# PCIe-M2.net
KiCad netlist of a schematic drawn in Altium Designer
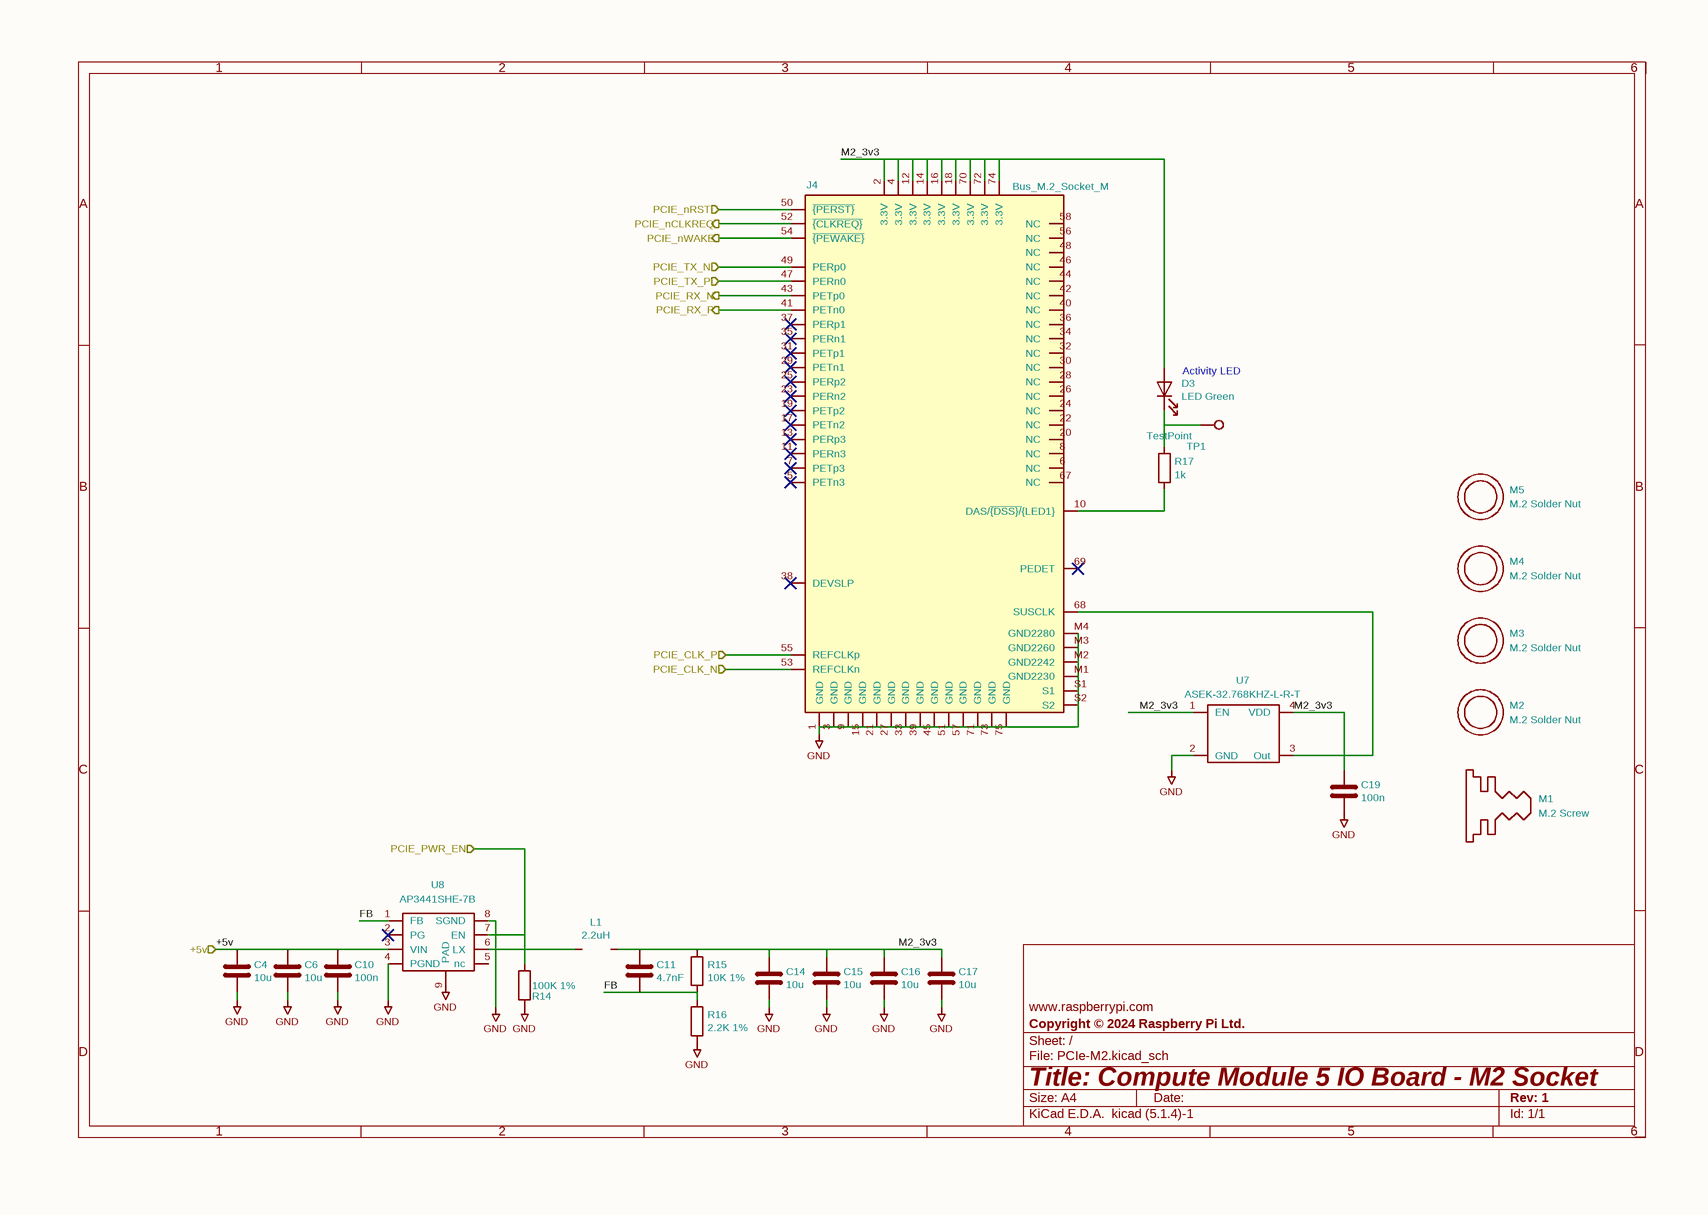
[diagram p0: PCIe-M2.SchDoc]

(export (version "E")
  (design (tool "Eeschema 10.0.6"))
  (components
    (comp (ref "C4") (value "10u") (libsource (lib "Device") (part "C")))
    (comp (ref "C6") (value "10u") (libsource (lib "Device") (part "C")))
    (comp (ref "C10") (value "100n") (libsource (lib "Device") (part "C")))
    (comp (ref "C11") (value "4.7nF") (libsource (lib "Device") (part "C")))
    (comp (ref "C14") (value "10u") (libsource (lib "Device") (part "C")))
    (comp (ref "C15") (value "10u") (libsource (lib "Device") (part "C")))
    (comp (ref "C16") (value "10u") (libsource (lib "Device") (part "C")))
    (comp (ref "C17") (value "10u") (libsource (lib "Device") (part "C")))
    (comp (ref "C19") (value "100n") (libsource (lib "Device") (part "C")))
    (comp (ref "D3") (value "LED Green") (libsource (lib "Device") (part "LED")))
    (comp (ref "J4")
      (value "Bus_M.2_Socket_M")
      (description "M.2 Socket 3 Mechanical Key M")
      (libsource (lib "CM5IO") (part "Bus_M.2_Socket_M"))
    )
    (comp (ref "L1") (value "2.2uH") (libsource (lib "Device") (part "L")))
    (comp (ref "M1") (value "M.2 Screw") (libsource (lib "CM5IO") (part "M.2_Screw")))
    (comp (ref "M2") (value "M.2 Solder Nut") (libsource (lib "CM5IO") (part "SolderNut")))
    (comp (ref "M3") (value "M.2 Solder Nut") (libsource (lib "CM5IO") (part "SolderNut")))
    (comp (ref "M4") (value "M.2 Solder Nut") (libsource (lib "CM5IO") (part "SolderNut")))
    (comp (ref "M5") (value "M.2 Solder Nut") (libsource (lib "CM5IO") (part "SolderNut")))
    (comp (ref "R14") (value "100K 1%") (libsource (lib "Device") (part "R")))
    (comp (ref "R15") (value "10K 1%") (libsource (lib "Device") (part "R")))
    (comp (ref "R16") (value "2.2K 1%") (libsource (lib "Device") (part "R")))
    (comp (ref "R17") (value "1k") (libsource (lib "Device") (part "R")))
    (comp (ref "TP1") (value "TestPoint") (libsource (lib "Connector") (part "TestPoint")))
    (comp (ref "U7") (value "ASEK-32.768KHZ-L-R-T") (libsource (lib "CM5IO") (part "ASEK-32.768KHZ-L-R-T")))
    (comp (ref "U8") (value "AP3441SHE-7B") (libsource (lib "CM5IO") (part "AP3441SHE-7B")))
  )
  (nets
    (net (code "1") (name "/+5v") (class "Default")
      (node (ref "C10") (pin "1") (pinfunction "1_1") (pintype "passive"))
      (node (ref "C4") (pin "1") (pinfunction "1_1") (pintype "passive"))
      (node (ref "C6") (pin "1") (pinfunction "1_1") (pintype "passive"))
      (node (ref "U8") (pin "3") (pinfunction "VIN_3") (pintype "passive"))
    )
    (net (code "2") (name "/FB") (class "Default")
      (node (ref "C11") (pin "2") (pinfunction "2_2") (pintype "passive"))
      (node (ref "R15") (pin "2") (pinfunction "2_2") (pintype "passive"))
      (node (ref "R16") (pin "1") (pinfunction "1_1") (pintype "passive"))
      (node (ref "U8") (pin "1") (pinfunction "FB_1") (pintype "passive"))
    )
    (net (code "3") (name "/M2_3v3") (class "Default")
      (node (ref "C11") (pin "1") (pinfunction "1_1") (pintype "passive"))
      (node (ref "C14") (pin "1") (pinfunction "1_1") (pintype "passive"))
      (node (ref "C15") (pin "1") (pinfunction "1_1") (pintype "passive"))
      (node (ref "C16") (pin "1") (pinfunction "1_1") (pintype "passive"))
      (node (ref "C17") (pin "1") (pinfunction "1_1") (pintype "passive"))
      (node (ref "C19") (pin "1") (pinfunction "1_1") (pintype "passive"))
      (node (ref "D3") (pin "2") (pinfunction "A_2") (pintype "passive"))
      (node (ref "J4") (pin "12") (pinfunction "3.3V_12") (pintype "passive"))
      (node (ref "J4") (pin "14") (pinfunction "3.3V_14") (pintype "passive"))
      (node (ref "J4") (pin "16") (pinfunction "3.3V_16") (pintype "passive"))
      (node (ref "J4") (pin "18") (pinfunction "3.3V_18") (pintype "passive"))
      (node (ref "J4") (pin "2") (pinfunction "3.3V_2") (pintype "passive"))
      (node (ref "J4") (pin "4") (pinfunction "3.3V_4") (pintype "passive"))
      (node (ref "J4") (pin "70") (pinfunction "3.3V_70") (pintype "passive"))
      (node (ref "J4") (pin "72") (pinfunction "3.3V_72") (pintype "passive"))
      (node (ref "J4") (pin "74") (pinfunction "3.3V_74") (pintype "passive"))
      (node (ref "L1") (pin "2") (pinfunction "2_2") (pintype "passive"))
      (node (ref "R15") (pin "1") (pinfunction "1_1") (pintype "passive"))
      (node (ref "U7") (pin "1") (pinfunction "EN_1") (pintype "passive"))
      (node (ref "U7") (pin "4") (pinfunction "VDD_4") (pintype "passive"))
    )
    (net (code "4") (name "/PCIE_CLK_N") (class "Default")
      (node (ref "J4") (pin "53") (pinfunction "REFCLKn_53") (pintype "passive"))
    )
    (net (code "5") (name "/PCIE_CLK_P") (class "Default")
      (node (ref "J4") (pin "55") (pinfunction "REFCLKp_55") (pintype "passive"))
    )
    (net (code "6") (name "/PCIE_PWR_EN") (class "Default")
      (node (ref "R14") (pin "1") (pinfunction "1_1") (pintype "passive"))
      (node (ref "U8") (pin "7") (pinfunction "EN_7") (pintype "passive"))
    )
    (net (code "7") (name "/PCIE_RX_N") (class "Default")
      (node (ref "J4") (pin "43") (pinfunction "PETp0_43") (pintype "passive"))
    )
    (net (code "8") (name "/PCIE_RX_P") (class "Default")
      (node (ref "J4") (pin "41") (pinfunction "PETn0_41") (pintype "passive"))
    )
    (net (code "9") (name "/PCIE_TX_N") (class "Default")
      (node (ref "J4") (pin "49") (pinfunction "PERp0_49") (pintype "passive"))
    )
    (net (code "10") (name "/PCIE_TX_P") (class "Default")
      (node (ref "J4") (pin "47") (pinfunction "PERn0_47") (pintype "passive"))
    )
    (net (code "11") (name "/PCIE_nCLKREQ") (class "Default")
      (node (ref "J4") (pin "52") (pinfunction "~{{CLKREQ}}_52") (pintype "passive"))
    )
    (net (code "12") (name "/PCIE_nRST") (class "Default")
      (node (ref "J4") (pin "50") (pinfunction "~{{PERST}}_50") (pintype "passive"))
    )
    (net (code "13") (name "/PCIE_nWAKE") (class "Default")
      (node (ref "J4") (pin "54") (pinfunction "~{{PEWAKE}}_54") (pintype "passive"))
    )
    (net (code "14") (name "GND") (class "Default")
      (node (ref "C10") (pin "2") (pinfunction "2_2") (pintype "passive"))
      (node (ref "C14") (pin "2") (pinfunction "2_2") (pintype "passive"))
      (node (ref "C15") (pin "2") (pinfunction "2_2") (pintype "passive"))
      (node (ref "C16") (pin "2") (pinfunction "2_2") (pintype "passive"))
      (node (ref "C17") (pin "2") (pinfunction "2_2") (pintype "passive"))
      (node (ref "C19") (pin "2") (pinfunction "2_2") (pintype "passive"))
      (node (ref "C4") (pin "2") (pinfunction "2_2") (pintype "passive"))
      (node (ref "C6") (pin "2") (pinfunction "2_2") (pintype "passive"))
      (node (ref "J4") (pin "1") (pinfunction "GND_1") (pintype "passive"))
      (node (ref "J4") (pin "15") (pinfunction "GND_15") (pintype "passive"))
      (node (ref "J4") (pin "21") (pinfunction "GND_21") (pintype "passive"))
      (node (ref "J4") (pin "27") (pinfunction "GND_27") (pintype "passive"))
      (node (ref "J4") (pin "3") (pinfunction "GND_3") (pintype "passive"))
      (node (ref "J4") (pin "33") (pinfunction "GND_33") (pintype "passive"))
      (node (ref "J4") (pin "39") (pinfunction "GND_39") (pintype "passive"))
      (node (ref "J4") (pin "45") (pinfunction "GND_45") (pintype "passive"))
      (node (ref "J4") (pin "51") (pinfunction "GND_51") (pintype "passive"))
      (node (ref "J4") (pin "57") (pinfunction "GND_57") (pintype "passive"))
      (node (ref "J4") (pin "71") (pinfunction "GND_71") (pintype "passive"))
      (node (ref "J4") (pin "73") (pinfunction "GND_73") (pintype "passive"))
      (node (ref "J4") (pin "75") (pinfunction "GND_75") (pintype "passive"))
      (node (ref "J4") (pin "9") (pinfunction "GND_9") (pintype "passive"))
      (node (ref "J4") (pin "M1") (pinfunction "GND2230_M1") (pintype "passive"))
      (node (ref "J4") (pin "M2") (pinfunction "GND2242_M2") (pintype "passive"))
      (node (ref "J4") (pin "M3") (pinfunction "GND2260_M3") (pintype "passive"))
      (node (ref "J4") (pin "M4") (pinfunction "GND2280_M4") (pintype "passive"))
      (node (ref "J4") (pin "S1") (pinfunction "S1_S1") (pintype "passive"))
      (node (ref "J4") (pin "S2") (pinfunction "S2_S2") (pintype "passive"))
      (node (ref "R14") (pin "2") (pinfunction "2_2") (pintype "passive"))
      (node (ref "R16") (pin "2") (pinfunction "2_2") (pintype "passive"))
      (node (ref "U7") (pin "2") (pinfunction "GND_2") (pintype "passive"))
      (node (ref "U8") (pin "4") (pinfunction "PGND_4") (pintype "passive"))
      (node (ref "U8") (pin "8") (pinfunction "SGND_8") (pintype "passive"))
      (node (ref "U8") (pin "9") (pinfunction "PAD_9") (pintype "passive"))
    )
    (net (code "15") (name "Net-(D3-K)") (class "Default")
      (node (ref "D3") (pin "1") (pinfunction "K_1") (pintype "passive"))
      (node (ref "R17") (pin "1") (pinfunction "1_1") (pintype "passive"))
      (node (ref "TP1") (pin "1") (pinfunction "1_1") (pintype "passive"))
    )
    (net (code "16") (name "Net-(J4-DAS{slash}~{{DSS}{slash}}{LED1})") (class "Default")
      (node (ref "J4") (pin "10") (pinfunction "DAS/~{{DSS}/}{LED1}_10") (pintype "passive"))
      (node (ref "R17") (pin "2") (pinfunction "2_2") (pintype "passive"))
    )
    (net (code "17") (name "Net-(J4-SUSCLK)") (class "Default")
      (node (ref "J4") (pin "68") (pinfunction "SUSCLK_68") (pintype "passive"))
      (node (ref "U7") (pin "3") (pinfunction "Out_3") (pintype "passive"))
    )
    (net (code "18") (name "Net-(U8-LX)") (class "Default")
      (node (ref "L1") (pin "1") (pinfunction "1_1") (pintype "passive"))
      (node (ref "U8") (pin "6") (pinfunction "LX_6") (pintype "passive"))
    )
    (net (code "19") (name "unconnected-(J4-DEVSLP-Pad38)") (class "Default")
      (node (ref "J4") (pin "38") (pinfunction "DEVSLP_38") (pintype "passive+no_connect"))
    )
    (net (code "20") (name "unconnected-(J4-NC-Pad6)") (class "Default")
      (node (ref "J4") (pin "6") (pinfunction "NC_6") (pintype "passive"))
    )
    (net (code "21") (name "unconnected-(J4-NC-Pad8)") (class "Default")
      (node (ref "J4") (pin "8") (pinfunction "NC_8") (pintype "passive"))
    )
    (net (code "22") (name "unconnected-(J4-NC-Pad20)") (class "Default")
      (node (ref "J4") (pin "20") (pinfunction "NC_20") (pintype "passive"))
    )
    (net (code "23") (name "unconnected-(J4-NC-Pad22)") (class "Default")
      (node (ref "J4") (pin "22") (pinfunction "NC_22") (pintype "passive"))
    )
    (net (code "24") (name "unconnected-(J4-NC-Pad24)") (class "Default")
      (node (ref "J4") (pin "24") (pinfunction "NC_24") (pintype "passive"))
    )
    (net (code "25") (name "unconnected-(J4-NC-Pad26)") (class "Default")
      (node (ref "J4") (pin "26") (pinfunction "NC_26") (pintype "passive"))
    )
    (net (code "26") (name "unconnected-(J4-NC-Pad28)") (class "Default")
      (node (ref "J4") (pin "28") (pinfunction "NC_28") (pintype "passive"))
    )
    (net (code "27") (name "unconnected-(J4-NC-Pad30)") (class "Default")
      (node (ref "J4") (pin "30") (pinfunction "NC_30") (pintype "passive"))
    )
    (net (code "28") (name "unconnected-(J4-NC-Pad32)") (class "Default")
      (node (ref "J4") (pin "32") (pinfunction "NC_32") (pintype "passive"))
    )
    (net (code "29") (name "unconnected-(J4-NC-Pad34)") (class "Default")
      (node (ref "J4") (pin "34") (pinfunction "NC_34") (pintype "passive"))
    )
    (net (code "30") (name "unconnected-(J4-NC-Pad36)") (class "Default")
      (node (ref "J4") (pin "36") (pinfunction "NC_36") (pintype "passive"))
    )
    (net (code "31") (name "unconnected-(J4-NC-Pad40)") (class "Default")
      (node (ref "J4") (pin "40") (pinfunction "NC_40") (pintype "passive"))
    )
    (net (code "32") (name "unconnected-(J4-NC-Pad42)") (class "Default")
      (node (ref "J4") (pin "42") (pinfunction "NC_42") (pintype "passive"))
    )
    (net (code "33") (name "unconnected-(J4-NC-Pad44)") (class "Default")
      (node (ref "J4") (pin "44") (pinfunction "NC_44") (pintype "passive"))
    )
    (net (code "34") (name "unconnected-(J4-NC-Pad46)") (class "Default")
      (node (ref "J4") (pin "46") (pinfunction "NC_46") (pintype "passive"))
    )
    (net (code "35") (name "unconnected-(J4-NC-Pad48)") (class "Default")
      (node (ref "J4") (pin "48") (pinfunction "NC_48") (pintype "passive"))
    )
    (net (code "36") (name "unconnected-(J4-NC-Pad56)") (class "Default")
      (node (ref "J4") (pin "56") (pinfunction "NC_56") (pintype "passive"))
    )
    (net (code "37") (name "unconnected-(J4-NC-Pad58)") (class "Default")
      (node (ref "J4") (pin "58") (pinfunction "NC_58") (pintype "passive"))
    )
    (net (code "38") (name "unconnected-(J4-NC-Pad67)") (class "Default")
      (node (ref "J4") (pin "67") (pinfunction "NC_67") (pintype "passive"))
    )
    (net (code "39") (name "unconnected-(J4-PEDET-Pad69)") (class "Default")
      (node (ref "J4") (pin "69") (pinfunction "PEDET_69") (pintype "passive+no_connect"))
    )
    (net (code "40") (name "unconnected-(J4-PERn1-Pad35)") (class "Default")
      (node (ref "J4") (pin "35") (pinfunction "PERn1_35") (pintype "passive+no_connect"))
    )
    (net (code "41") (name "unconnected-(J4-PERn2-Pad23)") (class "Default")
      (node (ref "J4") (pin "23") (pinfunction "PERn2_23") (pintype "passive+no_connect"))
    )
    (net (code "42") (name "unconnected-(J4-PERn3-Pad11)") (class "Default")
      (node (ref "J4") (pin "11") (pinfunction "PERn3_11") (pintype "passive+no_connect"))
    )
    (net (code "43") (name "unconnected-(J4-PERp1-Pad37)") (class "Default")
      (node (ref "J4") (pin "37") (pinfunction "PERp1_37") (pintype "passive+no_connect"))
    )
    (net (code "44") (name "unconnected-(J4-PERp2-Pad25)") (class "Default")
      (node (ref "J4") (pin "25") (pinfunction "PERp2_25") (pintype "passive+no_connect"))
    )
    (net (code "45") (name "unconnected-(J4-PERp3-Pad13)") (class "Default")
      (node (ref "J4") (pin "13") (pinfunction "PERp3_13") (pintype "passive+no_connect"))
    )
    (net (code "46") (name "unconnected-(J4-PETn1-Pad29)") (class "Default")
      (node (ref "J4") (pin "29") (pinfunction "PETn1_29") (pintype "passive+no_connect"))
    )
    (net (code "47") (name "unconnected-(J4-PETn2-Pad17)") (class "Default")
      (node (ref "J4") (pin "17") (pinfunction "PETn2_17") (pintype "passive+no_connect"))
    )
    (net (code "48") (name "unconnected-(J4-PETn3-Pad5)") (class "Default")
      (node (ref "J4") (pin "5") (pinfunction "PETn3_5") (pintype "passive+no_connect"))
    )
    (net (code "49") (name "unconnected-(J4-PETp1-Pad31)") (class "Default")
      (node (ref "J4") (pin "31") (pinfunction "PETp1_31") (pintype "passive+no_connect"))
    )
    (net (code "50") (name "unconnected-(J4-PETp2-Pad19)") (class "Default")
      (node (ref "J4") (pin "19") (pinfunction "PETp2_19") (pintype "passive+no_connect"))
    )
    (net (code "51") (name "unconnected-(J4-PETp3-Pad7)") (class "Default")
      (node (ref "J4") (pin "7") (pinfunction "PETp3_7") (pintype "passive+no_connect"))
    )
    (net (code "52") (name "unconnected-(U8-PG-Pad2)") (class "Default")
      (node (ref "U8") (pin "2") (pinfunction "PG_2") (pintype "passive+no_connect"))
    )
    (net (code "53") (name "unconnected-(U8-nc-Pad5)") (class "Default")
      (node (ref "U8") (pin "5") (pinfunction "nc_5") (pintype "passive"))
    )
  )
)
